# Extender_FPGA.net
KiCad netlist of a schematic drawn in Altium Designer
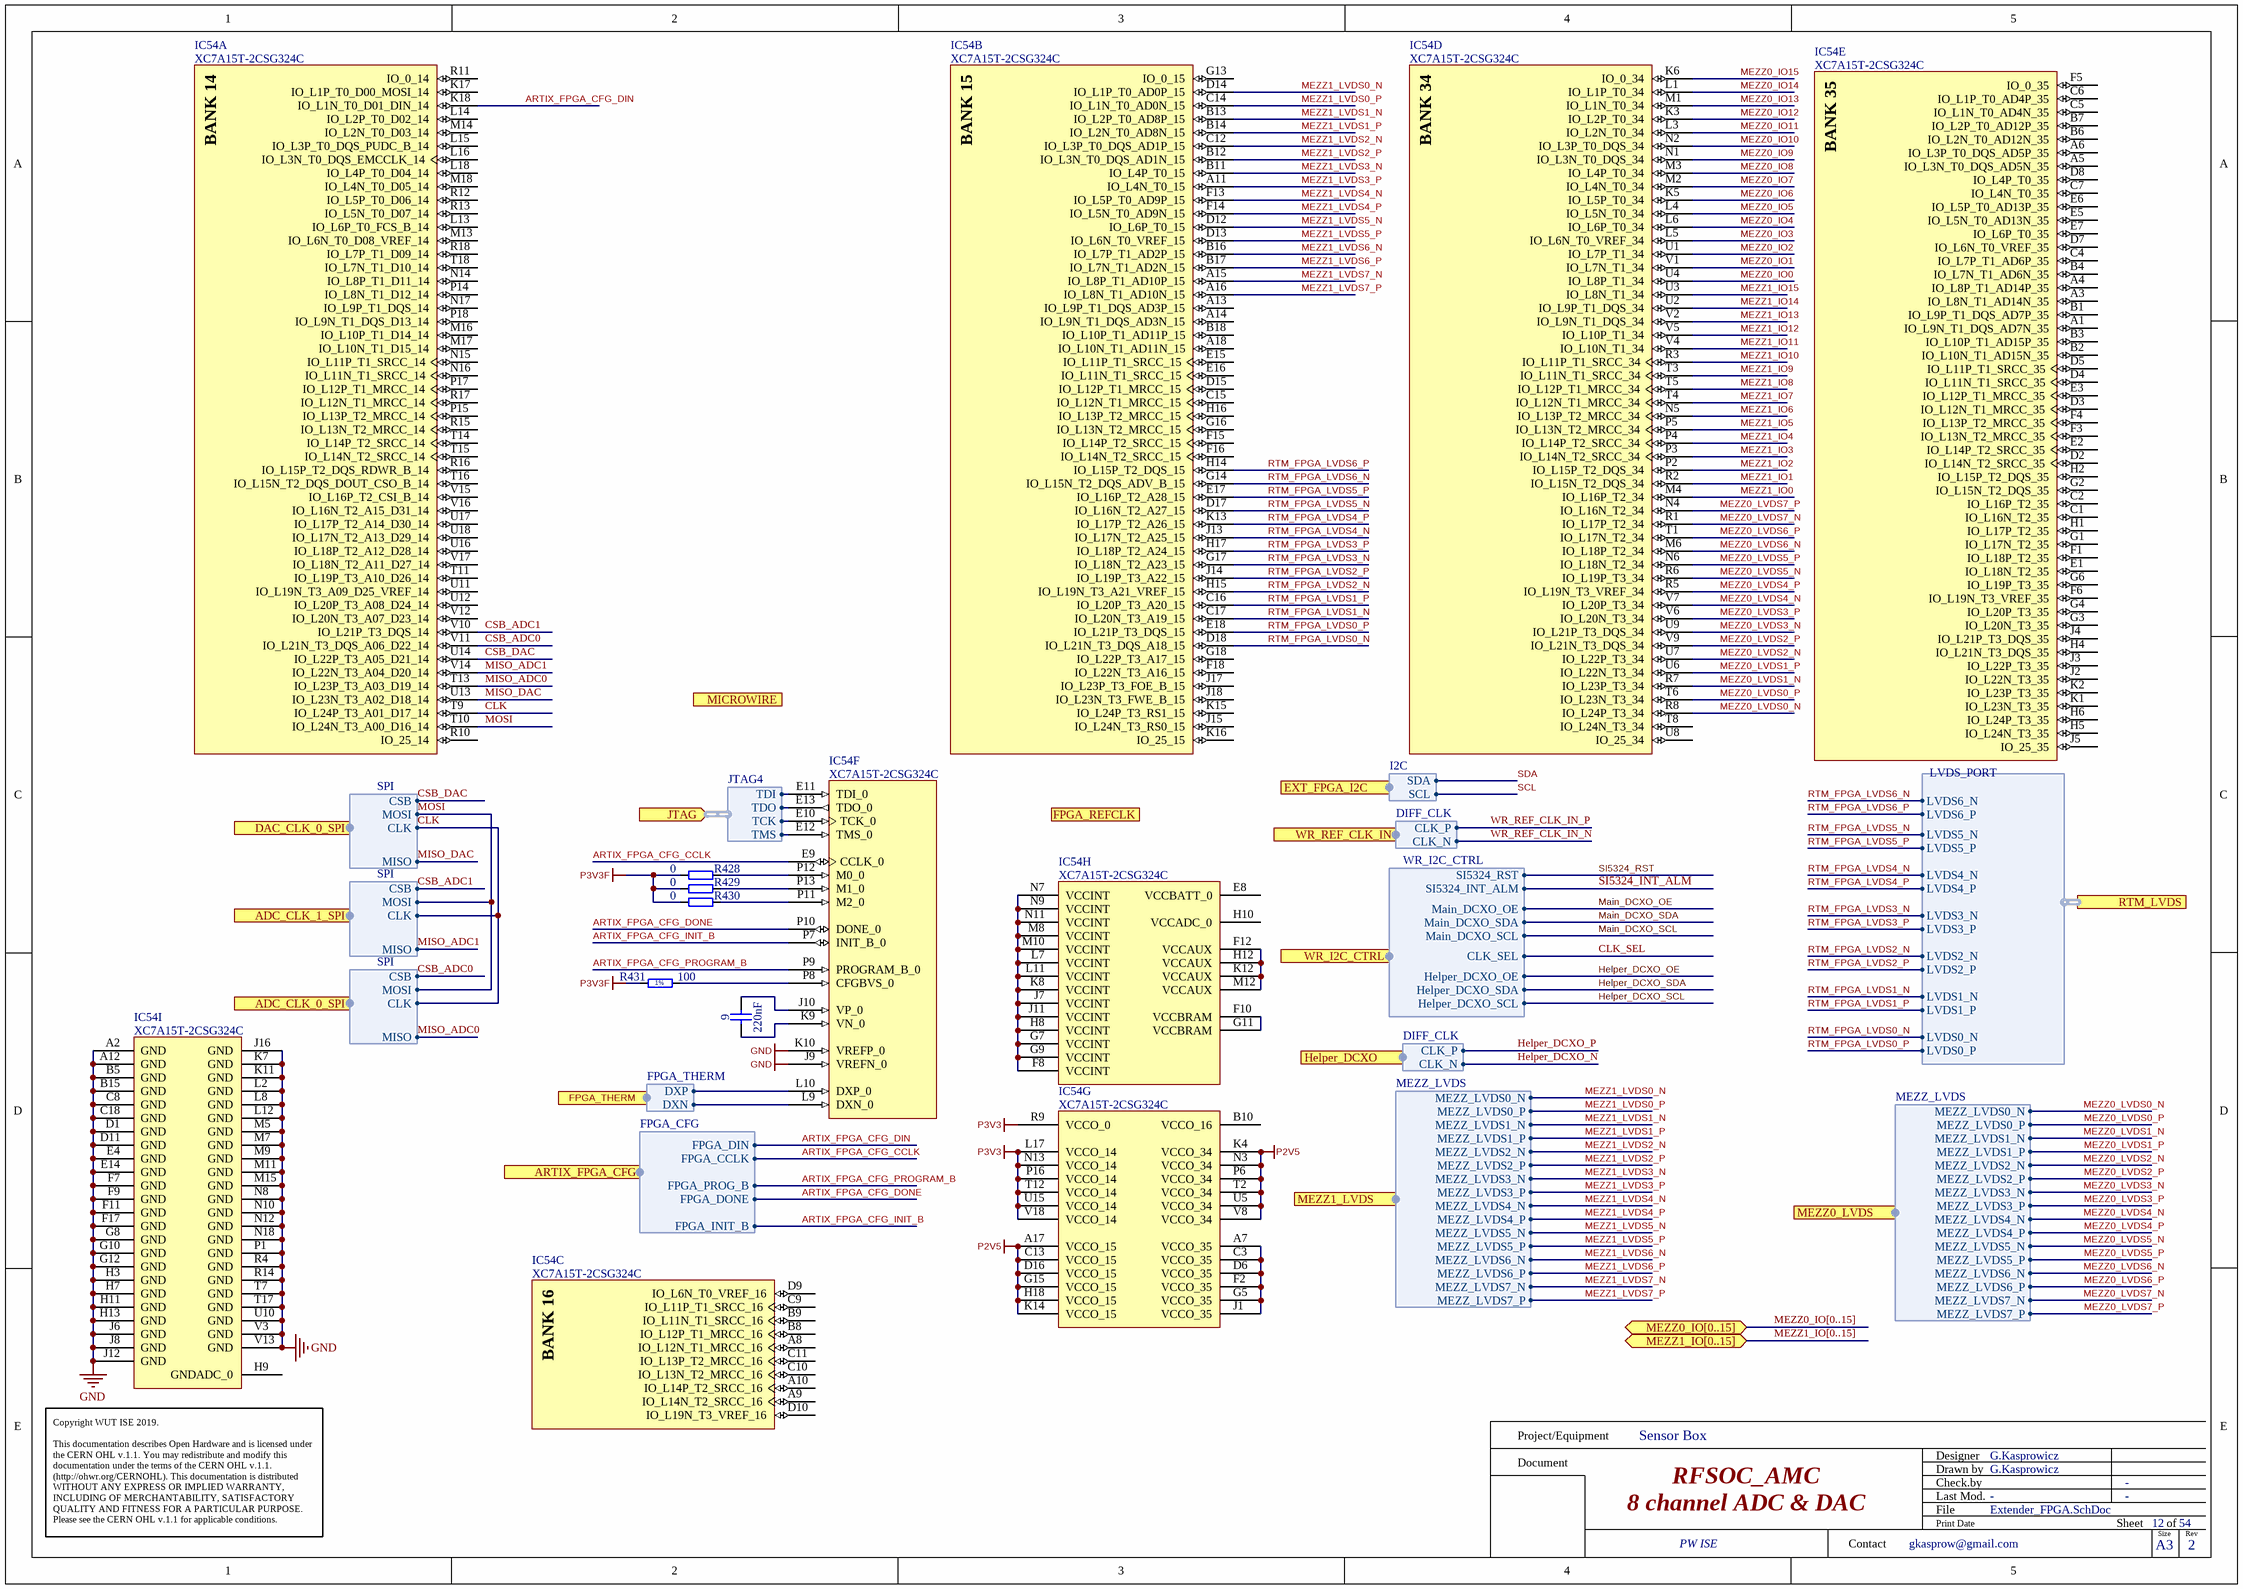
[diagram p0: Extender_FPGA.SchDoc]

(export (version "E")
  (design (tool "Eeschema 10.0.6"))
  (components
    (comp (ref "9")
      (value "220nF")
      (footprint "CAPC0603X33N")
      (description "Non-polarised capacitor")
      (fields
        (field (name "MANUFACTURER PART NUMBER") "CC0201_220NF_6.3V_20%_X5R")
        (field (name "MANUFACTURER") "GENERIC")
        (field (name "AUTHOR") "CERN DEM JLC")
      )
      (libsource (lib "Capacitors") (part "Capacitor - non polarized"))
    )
    (comp (ref "IC54")
      (value "XC7A15T-2CSG324C")
      (footprint "BGA324C80P18X18_1500X1500X150")
      (description "Artix-7 FPGA, 210 User I/Os, 0 GTP, 324-Ball BGA, Speed Grade 2, Commercial Grade, Pb-Free")
      (fields (field (name "MANUFACTURER") "XILINX") (field (name "AUTHOR") "CERN DEM MR"))
      (libsource (lib "ICs And Semiconductors") (part "XC7A15T-2CSG324C"))
    )
    (comp (ref "R428")
      (value "0")
      (footprint "RESC1005X40N")
      (description "Resistor")
      (fields
        (field (name "MANUFACTURER PART NUMBER") "R0402_0R_JUMPER")
        (field (name "MANUFACTURER") "GENERIC")
        (field (name "AUTHOR") "CERN DEM JLC")
      )
      (libsource (lib "Resistors") (part "Resistor"))
    )
    (comp (ref "R429")
      (value "0")
      (footprint "RESC1005X40N")
      (description "Resistor")
      (fields
        (field (name "MANUFACTURER PART NUMBER") "R0402_0R_JUMPER")
        (field (name "MANUFACTURER") "GENERIC")
        (field (name "AUTHOR") "CERN DEM JLC")
      )
      (libsource (lib "Resistors") (part "Resistor"))
    )
    (comp (ref "R430")
      (value "0")
      (footprint "RESC1005X40N")
      (description "Resistor")
      (fields
        (field (name "MANUFACTURER PART NUMBER") "R0402_0R_JUMPER")
        (field (name "MANUFACTURER") "GENERIC")
        (field (name "AUTHOR") "CERN DEM JLC")
      )
      (libsource (lib "Resistors") (part "Resistor"))
    )
    (comp (ref "R431")
      (value "100")
      (footprint "RESC1005X40N")
      (description "Resistor - 1%")
      (fields
        (field (name "MANUFACTURER PART NUMBER") "R0402_100R_1%_0.1W_100PPM_50V")
        (field (name "MANUFACTURER") "GENERIC")
        (field (name "AUTHOR") "CERN DEM JLC")
      )
      (libsource (lib "Resistors") (part "Resistor - 1%"))
    )
  )
  (nets
    (net (code "11") (name "/ARTIX_FPGA_CFG_CCLK") (class "Default")
      (node (ref "IC54") (pin "E9") (pinfunction "CCLK_0_E9") (pintype "bidirectional"))
    )
    (net (code "12") (name "/ARTIX_FPGA_CFG_DIN") (class "Default")
      (node (ref "IC54") (pin "K18") (pinfunction "IO_L1N_T0_D01_DIN_14_K18") (pintype "bidirectional"))
    )
    (net (code "13") (name "/ARTIX_FPGA_CFG_DONE") (class "Default")
      (node (ref "IC54") (pin "P10") (pinfunction "DONE_0_P10") (pintype "bidirectional"))
    )
    (net (code "14") (name "/ARTIX_FPGA_CFG_INIT_B") (class "Default")
      (node (ref "IC54") (pin "P7") (pinfunction "INIT_B_0_P7") (pintype "bidirectional"))
    )
    (net (code "15") (name "/ARTIX_FPGA_CFG_PROGRAM_B") (class "Default")
      (node (ref "IC54") (pin "P9") (pinfunction "PROGRAM_B_0_P9") (pintype "input"))
    )
    (net (code "16") (name "/CLK") (class "Default")
      (node (ref "IC54") (pin "T9") (pinfunction "IO_L24P_T3_A01_D17_14_T9") (pintype "bidirectional"))
    )
    (net (code "18") (name "/CSB_ADC0") (class "Default")
      (node (ref "IC54") (pin "V11") (pinfunction "IO_L21N_T3_DQS_A06_D22_14_V11") (pintype "bidirectional"))
    )
    (net (code "19") (name "/CSB_ADC1") (class "Default")
      (node (ref "IC54") (pin "V10") (pinfunction "IO_L21P_T3_DQS_14_V10") (pintype "bidirectional"))
    )
    (net (code "20") (name "/CSB_DAC") (class "Default")
      (node (ref "IC54") (pin "U14") (pinfunction "IO_L22P_T3_A05_D21_14_U14") (pintype "bidirectional"))
    )
    (net (code "21") (name "/DXN") (class "Default")
      (node (ref "IC54") (pin "L9") (pinfunction "DXN_0_L9") (pintype "input"))
    )
    (net (code "22") (name "/DXP") (class "Default")
      (node (ref "IC54") (pin "L10") (pinfunction "DXP_0_L10") (pintype "input"))
    )
    (net (code "29") (name "/MEZZ0_IO0") (class "Default")
      (node (ref "IC54") (pin "U4") (pinfunction "IO_L8P_T1_34_U4") (pintype "bidirectional"))
    )
    (net (code "30") (name "/MEZZ0_IO1") (class "Default")
      (node (ref "IC54") (pin "V1") (pinfunction "IO_L7N_T1_34_V1") (pintype "bidirectional"))
    )
    (net (code "31") (name "/MEZZ0_IO2") (class "Default")
      (node (ref "IC54") (pin "U1") (pinfunction "IO_L7P_T1_34_U1") (pintype "bidirectional"))
    )
    (net (code "32") (name "/MEZZ0_IO3") (class "Default")
      (node (ref "IC54") (pin "L5") (pinfunction "IO_L6N_T0_VREF_34_L5") (pintype "bidirectional"))
    )
    (net (code "33") (name "/MEZZ0_IO4") (class "Default")
      (node (ref "IC54") (pin "L6") (pinfunction "IO_L6P_T0_34_L6") (pintype "bidirectional"))
    )
    (net (code "34") (name "/MEZZ0_IO5") (class "Default")
      (node (ref "IC54") (pin "L4") (pinfunction "IO_L5N_T0_34_L4") (pintype "bidirectional"))
    )
    (net (code "35") (name "/MEZZ0_IO6") (class "Default")
      (node (ref "IC54") (pin "K5") (pinfunction "IO_L5P_T0_34_K5") (pintype "bidirectional"))
    )
    (net (code "36") (name "/MEZZ0_IO7") (class "Default")
      (node (ref "IC54") (pin "M2") (pinfunction "IO_L4N_T0_34_M2") (pintype "bidirectional"))
    )
    (net (code "37") (name "/MEZZ0_IO8") (class "Default")
      (node (ref "IC54") (pin "M3") (pinfunction "IO_L4P_T0_34_M3") (pintype "bidirectional"))
    )
    (net (code "38") (name "/MEZZ0_IO9") (class "Default")
      (node (ref "IC54") (pin "N1") (pinfunction "IO_L3N_T0_DQS_34_N1") (pintype "bidirectional"))
    )
    (net (code "39") (name "/MEZZ0_IO10") (class "Default")
      (node (ref "IC54") (pin "N2") (pinfunction "IO_L3P_T0_DQS_34_N2") (pintype "bidirectional"))
    )
    (net (code "40") (name "/MEZZ0_IO11") (class "Default")
      (node (ref "IC54") (pin "L3") (pinfunction "IO_L2N_T0_34_L3") (pintype "bidirectional"))
    )
    (net (code "41") (name "/MEZZ0_IO12") (class "Default")
      (node (ref "IC54") (pin "K3") (pinfunction "IO_L2P_T0_34_K3") (pintype "bidirectional"))
    )
    (net (code "42") (name "/MEZZ0_IO13") (class "Default")
      (node (ref "IC54") (pin "M1") (pinfunction "IO_L1N_T0_34_M1") (pintype "bidirectional"))
    )
    (net (code "43") (name "/MEZZ0_IO14") (class "Default")
      (node (ref "IC54") (pin "L1") (pinfunction "IO_L1P_T0_34_L1") (pintype "bidirectional"))
    )
    (net (code "44") (name "/MEZZ0_IO15") (class "Default")
      (node (ref "IC54") (pin "K6") (pinfunction "IO_0_34_K6") (pintype "bidirectional"))
    )
    (net (code "46") (name "/MEZZ0_LVDS0_N") (class "Default")
      (node (ref "IC54") (pin "R8") (pinfunction "IO_L24P_T3_34_R8") (pintype "bidirectional"))
    )
    (net (code "47") (name "/MEZZ0_LVDS0_P") (class "Default")
      (node (ref "IC54") (pin "T6") (pinfunction "IO_L23N_T3_34_T6") (pintype "bidirectional"))
    )
    (net (code "48") (name "/MEZZ0_LVDS1_N") (class "Default")
      (node (ref "IC54") (pin "R7") (pinfunction "IO_L23P_T3_34_R7") (pintype "bidirectional"))
    )
    (net (code "49") (name "/MEZZ0_LVDS1_P") (class "Default")
      (node (ref "IC54") (pin "U6") (pinfunction "IO_L22N_T3_34_U6") (pintype "bidirectional"))
    )
    (net (code "50") (name "/MEZZ0_LVDS2_N") (class "Default")
      (node (ref "IC54") (pin "U7") (pinfunction "IO_L22P_T3_34_U7") (pintype "bidirectional"))
    )
    (net (code "51") (name "/MEZZ0_LVDS2_P") (class "Default")
      (node (ref "IC54") (pin "V9") (pinfunction "IO_L21N_T3_DQS_34_V9") (pintype "bidirectional"))
    )
    (net (code "52") (name "/MEZZ0_LVDS3_N") (class "Default")
      (node (ref "IC54") (pin "U9") (pinfunction "IO_L21P_T3_DQS_34_U9") (pintype "bidirectional"))
    )
    (net (code "53") (name "/MEZZ0_LVDS3_P") (class "Default")
      (node (ref "IC54") (pin "V6") (pinfunction "IO_L20N_T3_34_V6") (pintype "bidirectional"))
    )
    (net (code "54") (name "/MEZZ0_LVDS4_N") (class "Default")
      (node (ref "IC54") (pin "V7") (pinfunction "IO_L20P_T3_34_V7") (pintype "bidirectional"))
    )
    (net (code "55") (name "/MEZZ0_LVDS4_P") (class "Default")
      (node (ref "IC54") (pin "R5") (pinfunction "IO_L19N_T3_VREF_34_R5") (pintype "bidirectional"))
    )
    (net (code "56") (name "/MEZZ0_LVDS5_N") (class "Default")
      (node (ref "IC54") (pin "R6") (pinfunction "IO_L19P_T3_34_R6") (pintype "bidirectional"))
    )
    (net (code "57") (name "/MEZZ0_LVDS5_P") (class "Default")
      (node (ref "IC54") (pin "N6") (pinfunction "IO_L18N_T2_34_N6") (pintype "bidirectional"))
    )
    (net (code "58") (name "/MEZZ0_LVDS6_N") (class "Default")
      (node (ref "IC54") (pin "M6") (pinfunction "IO_L18P_T2_34_M6") (pintype "bidirectional"))
    )
    (net (code "59") (name "/MEZZ0_LVDS6_P") (class "Default")
      (node (ref "IC54") (pin "T1") (pinfunction "IO_L17N_T2_34_T1") (pintype "bidirectional"))
    )
    (net (code "60") (name "/MEZZ0_LVDS7_N") (class "Default")
      (node (ref "IC54") (pin "R1") (pinfunction "IO_L17P_T2_34_R1") (pintype "bidirectional"))
    )
    (net (code "61") (name "/MEZZ0_LVDS7_P") (class "Default")
      (node (ref "IC54") (pin "N4") (pinfunction "IO_L16N_T2_34_N4") (pintype "bidirectional"))
    )
    (net (code "62") (name "/MEZZ1_IO0") (class "Default")
      (node (ref "IC54") (pin "M4") (pinfunction "IO_L16P_T2_34_M4") (pintype "bidirectional"))
    )
    (net (code "63") (name "/MEZZ1_IO1") (class "Default")
      (node (ref "IC54") (pin "R2") (pinfunction "IO_L15N_T2_DQS_34_R2") (pintype "bidirectional"))
    )
    (net (code "64") (name "/MEZZ1_IO2") (class "Default")
      (node (ref "IC54") (pin "P2") (pinfunction "IO_L15P_T2_DQS_34_P2") (pintype "bidirectional"))
    )
    (net (code "65") (name "/MEZZ1_IO3") (class "Default")
      (node (ref "IC54") (pin "P3") (pinfunction "IO_L14N_T2_SRCC_34_P3") (pintype "bidirectional"))
    )
    (net (code "66") (name "/MEZZ1_IO4") (class "Default")
      (node (ref "IC54") (pin "P4") (pinfunction "IO_L14P_T2_SRCC_34_P4") (pintype "bidirectional"))
    )
    (net (code "67") (name "/MEZZ1_IO5") (class "Default")
      (node (ref "IC54") (pin "P5") (pinfunction "IO_L13N_T2_MRCC_34_P5") (pintype "bidirectional"))
    )
    (net (code "68") (name "/MEZZ1_IO6") (class "Default")
      (node (ref "IC54") (pin "N5") (pinfunction "IO_L13P_T2_MRCC_34_N5") (pintype "bidirectional"))
    )
    (net (code "69") (name "/MEZZ1_IO7") (class "Default")
      (node (ref "IC54") (pin "T4") (pinfunction "IO_L12N_T1_MRCC_34_T4") (pintype "bidirectional"))
    )
    (net (code "70") (name "/MEZZ1_IO8") (class "Default")
      (node (ref "IC54") (pin "T5") (pinfunction "IO_L12P_T1_MRCC_34_T5") (pintype "bidirectional"))
    )
    (net (code "71") (name "/MEZZ1_IO9") (class "Default")
      (node (ref "IC54") (pin "T3") (pinfunction "IO_L11N_T1_SRCC_34_T3") (pintype "bidirectional"))
    )
    (net (code "72") (name "/MEZZ1_IO10") (class "Default")
      (node (ref "IC54") (pin "R3") (pinfunction "IO_L11P_T1_SRCC_34_R3") (pintype "bidirectional"))
    )
    (net (code "73") (name "/MEZZ1_IO11") (class "Default")
      (node (ref "IC54") (pin "V4") (pinfunction "IO_L10N_T1_34_V4") (pintype "bidirectional"))
    )
    (net (code "74") (name "/MEZZ1_IO12") (class "Default")
      (node (ref "IC54") (pin "V5") (pinfunction "IO_L10P_T1_34_V5") (pintype "bidirectional"))
    )
    (net (code "75") (name "/MEZZ1_IO13") (class "Default")
      (node (ref "IC54") (pin "V2") (pinfunction "IO_L9N_T1_DQS_34_V2") (pintype "bidirectional"))
    )
    (net (code "76") (name "/MEZZ1_IO14") (class "Default")
      (node (ref "IC54") (pin "U2") (pinfunction "IO_L9P_T1_DQS_34_U2") (pintype "bidirectional"))
    )
    (net (code "77") (name "/MEZZ1_IO15") (class "Default")
      (node (ref "IC54") (pin "U3") (pinfunction "IO_L8N_T1_34_U3") (pintype "bidirectional"))
    )
    (net (code "79") (name "/MEZZ1_LVDS0_N") (class "Default")
      (node (ref "IC54") (pin "D14") (pinfunction "IO_L1P_T0_AD0P_15_D14") (pintype "bidirectional"))
    )
    (net (code "80") (name "/MEZZ1_LVDS0_P") (class "Default")
      (node (ref "IC54") (pin "C14") (pinfunction "IO_L1N_T0_AD0N_15_C14") (pintype "bidirectional"))
    )
    (net (code "81") (name "/MEZZ1_LVDS1_N") (class "Default")
      (node (ref "IC54") (pin "B13") (pinfunction "IO_L2P_T0_AD8P_15_B13") (pintype "bidirectional"))
    )
    (net (code "82") (name "/MEZZ1_LVDS1_P") (class "Default")
      (node (ref "IC54") (pin "B14") (pinfunction "IO_L2N_T0_AD8N_15_B14") (pintype "bidirectional"))
    )
    (net (code "83") (name "/MEZZ1_LVDS2_N") (class "Default")
      (node (ref "IC54") (pin "C12") (pinfunction "IO_L3P_T0_DQS_AD1P_15_C12") (pintype "bidirectional"))
    )
    (net (code "84") (name "/MEZZ1_LVDS2_P") (class "Default")
      (node (ref "IC54") (pin "B12") (pinfunction "IO_L3N_T0_DQS_AD1N_15_B12") (pintype "bidirectional"))
    )
    (net (code "85") (name "/MEZZ1_LVDS3_N") (class "Default")
      (node (ref "IC54") (pin "B11") (pinfunction "IO_L4P_T0_15_B11") (pintype "bidirectional"))
    )
    (net (code "86") (name "/MEZZ1_LVDS3_P") (class "Default")
      (node (ref "IC54") (pin "A11") (pinfunction "IO_L4N_T0_15_A11") (pintype "bidirectional"))
    )
    (net (code "87") (name "/MEZZ1_LVDS4_N") (class "Default")
      (node (ref "IC54") (pin "F13") (pinfunction "IO_L5P_T0_AD9P_15_F13") (pintype "bidirectional"))
    )
    (net (code "88") (name "/MEZZ1_LVDS4_P") (class "Default")
      (node (ref "IC54") (pin "F14") (pinfunction "IO_L5N_T0_AD9N_15_F14") (pintype "bidirectional"))
    )
    (net (code "89") (name "/MEZZ1_LVDS5_N") (class "Default")
      (node (ref "IC54") (pin "D12") (pinfunction "IO_L6P_T0_15_D12") (pintype "bidirectional"))
    )
    (net (code "90") (name "/MEZZ1_LVDS5_P") (class "Default")
      (node (ref "IC54") (pin "D13") (pinfunction "IO_L6N_T0_VREF_15_D13") (pintype "bidirectional"))
    )
    (net (code "91") (name "/MEZZ1_LVDS6_N") (class "Default")
      (node (ref "IC54") (pin "B16") (pinfunction "IO_L7P_T1_AD2P_15_B16") (pintype "bidirectional"))
    )
    (net (code "92") (name "/MEZZ1_LVDS6_P") (class "Default")
      (node (ref "IC54") (pin "B17") (pinfunction "IO_L7N_T1_AD2N_15_B17") (pintype "bidirectional"))
    )
    (net (code "93") (name "/MEZZ1_LVDS7_N") (class "Default")
      (node (ref "IC54") (pin "A15") (pinfunction "IO_L8P_T1_AD10P_15_A15") (pintype "bidirectional"))
    )
    (net (code "94") (name "/MEZZ1_LVDS7_P") (class "Default")
      (node (ref "IC54") (pin "A16") (pinfunction "IO_L8N_T1_AD10N_15_A16") (pintype "bidirectional"))
    )
    (net (code "96") (name "/MISO_ADC0") (class "Default")
      (node (ref "IC54") (pin "T13") (pinfunction "IO_L23P_T3_A03_D19_14_T13") (pintype "bidirectional"))
    )
    (net (code "97") (name "/MISO_ADC1") (class "Default")
      (node (ref "IC54") (pin "V14") (pinfunction "IO_L22N_T3_A04_D20_14_V14") (pintype "bidirectional"))
    )
    (net (code "98") (name "/MISO_DAC") (class "Default")
      (node (ref "IC54") (pin "U13") (pinfunction "IO_L23N_T3_A02_D18_14_U13") (pintype "bidirectional"))
    )
    (net (code "99") (name "/MOSI") (class "Default")
      (node (ref "IC54") (pin "T10") (pinfunction "IO_L24N_T3_A00_D16_14_T10") (pintype "bidirectional"))
    )
    (net (code "103") (name "/RTM_FPGA_LVDS0_N") (class "Default")
      (node (ref "IC54") (pin "D18") (pinfunction "IO_L21N_T3_DQS_A18_15_D18") (pintype "bidirectional"))
    )
    (net (code "104") (name "/RTM_FPGA_LVDS0_P") (class "Default")
      (node (ref "IC54") (pin "E18") (pinfunction "IO_L21P_T3_DQS_15_E18") (pintype "bidirectional"))
    )
    (net (code "105") (name "/RTM_FPGA_LVDS1_N") (class "Default")
      (node (ref "IC54") (pin "C17") (pinfunction "IO_L20N_T3_A19_15_C17") (pintype "bidirectional"))
    )
    (net (code "106") (name "/RTM_FPGA_LVDS1_P") (class "Default")
      (node (ref "IC54") (pin "C16") (pinfunction "IO_L20P_T3_A20_15_C16") (pintype "bidirectional"))
    )
    (net (code "107") (name "/RTM_FPGA_LVDS2_N") (class "Default")
      (node (ref "IC54") (pin "H15") (pinfunction "IO_L19N_T3_A21_VREF_15_H15") (pintype "bidirectional"))
    )
    (net (code "108") (name "/RTM_FPGA_LVDS2_P") (class "Default")
      (node (ref "IC54") (pin "J14") (pinfunction "IO_L19P_T3_A22_15_J14") (pintype "bidirectional"))
    )
    (net (code "109") (name "/RTM_FPGA_LVDS3_N") (class "Default")
      (node (ref "IC54") (pin "G17") (pinfunction "IO_L18N_T2_A23_15_G17") (pintype "bidirectional"))
    )
    (net (code "110") (name "/RTM_FPGA_LVDS3_P") (class "Default")
      (node (ref "IC54") (pin "H17") (pinfunction "IO_L18P_T2_A24_15_H17") (pintype "bidirectional"))
    )
    (net (code "111") (name "/RTM_FPGA_LVDS4_N") (class "Default")
      (node (ref "IC54") (pin "J13") (pinfunction "IO_L17N_T2_A25_15_J13") (pintype "bidirectional"))
    )
    (net (code "112") (name "/RTM_FPGA_LVDS4_P") (class "Default")
      (node (ref "IC54") (pin "K13") (pinfunction "IO_L17P_T2_A26_15_K13") (pintype "bidirectional"))
    )
    (net (code "113") (name "/RTM_FPGA_LVDS5_N") (class "Default")
      (node (ref "IC54") (pin "D17") (pinfunction "IO_L16N_T2_A27_15_D17") (pintype "bidirectional"))
    )
    (net (code "114") (name "/RTM_FPGA_LVDS5_P") (class "Default")
      (node (ref "IC54") (pin "E17") (pinfunction "IO_L16P_T2_A28_15_E17") (pintype "bidirectional"))
    )
    (net (code "115") (name "/RTM_FPGA_LVDS6_N") (class "Default")
      (node (ref "IC54") (pin "G14") (pinfunction "IO_L15N_T2_DQS_ADV_B_15_G14") (pintype "bidirectional"))
    )
    (net (code "116") (name "/RTM_FPGA_LVDS6_P") (class "Default")
      (node (ref "IC54") (pin "H14") (pinfunction "IO_L15P_T2_DQS_15_H14") (pintype "bidirectional"))
    )
    (net (code "121") (name "/TCK") (class "Default")
      (node (ref "IC54") (pin "E10") (pinfunction "TCK_0_E10") (pintype "input"))
    )
    (net (code "122") (name "/TDI") (class "Default")
      (node (ref "IC54") (pin "E11") (pinfunction "TDI_0_E11") (pintype "input"))
    )
    (net (code "123") (name "/TDO") (class "Default")
      (node (ref "IC54") (pin "E13") (pinfunction "TDO_0_E13") (pintype "output"))
    )
    (net (code "124") (name "/TMS") (class "Default")
      (node (ref "IC54") (pin "E12") (pinfunction "TMS_0_E12") (pintype "input"))
    )
    (net (code "136") (name "GND") (class "Default")
      (node (ref "IC54") (pin "A12") (pinfunction "GND_A12") (pintype "power_in"))
      (node (ref "IC54") (pin "A2") (pinfunction "GND_A2") (pintype "power_in"))
      (node (ref "IC54") (pin "B15") (pinfunction "GND_B15") (pintype "power_in"))
      (node (ref "IC54") (pin "B5") (pinfunction "GND_B5") (pintype "power_in"))
      (node (ref "IC54") (pin "C18") (pinfunction "GND_C18") (pintype "power_in"))
      (node (ref "IC54") (pin "C8") (pinfunction "GND_C8") (pintype "power_in"))
      (node (ref "IC54") (pin "D1") (pinfunction "GND_D1") (pintype "power_in"))
      (node (ref "IC54") (pin "D11") (pinfunction "GND_D11") (pintype "power_in"))
      (node (ref "IC54") (pin "E14") (pinfunction "GND_E14") (pintype "power_in"))
      (node (ref "IC54") (pin "E4") (pinfunction "GND_E4") (pintype "power_in"))
      (node (ref "IC54") (pin "F11") (pinfunction "GND_F11") (pintype "power_in"))
      (node (ref "IC54") (pin "F17") (pinfunction "GND_F17") (pintype "power_in"))
      (node (ref "IC54") (pin "F7") (pinfunction "GND_F7") (pintype "power_in"))
      (node (ref "IC54") (pin "F9") (pinfunction "GND_F9") (pintype "power_in"))
      (node (ref "IC54") (pin "G10") (pinfunction "GND_G10") (pintype "power_in"))
      (node (ref "IC54") (pin "G12") (pinfunction "GND_G12") (pintype "power_in"))
      (node (ref "IC54") (pin "G8") (pinfunction "GND_G8") (pintype "power_in"))
      (node (ref "IC54") (pin "H11") (pinfunction "GND_H11") (pintype "power_in"))
      (node (ref "IC54") (pin "H13") (pinfunction "GND_H13") (pintype "power_in"))
      (node (ref "IC54") (pin "H3") (pinfunction "GND_H3") (pintype "power_in"))
      (node (ref "IC54") (pin "H7") (pinfunction "GND_H7") (pintype "power_in"))
      (node (ref "IC54") (pin "J12") (pinfunction "GND_J12") (pintype "power_in"))
      (node (ref "IC54") (pin "J16") (pinfunction "GND_J16") (pintype "power_in"))
      (node (ref "IC54") (pin "J6") (pinfunction "GND_J6") (pintype "power_in"))
      (node (ref "IC54") (pin "J8") (pinfunction "GND_J8") (pintype "power_in"))
      (node (ref "IC54") (pin "J9") (pinfunction "VREFN_0_J9") (pintype "input"))
      (node (ref "IC54") (pin "K10") (pinfunction "VREFP_0_K10") (pintype "input"))
      (node (ref "IC54") (pin "K11") (pinfunction "GND_K11") (pintype "power_in"))
      (node (ref "IC54") (pin "K7") (pinfunction "GND_K7") (pintype "power_in"))
      (node (ref "IC54") (pin "L12") (pinfunction "GND_L12") (pintype "power_in"))
      (node (ref "IC54") (pin "L2") (pinfunction "GND_L2") (pintype "power_in"))
      (node (ref "IC54") (pin "L8") (pinfunction "GND_L8") (pintype "power_in"))
      (node (ref "IC54") (pin "M11") (pinfunction "GND_M11") (pintype "power_in"))
      (node (ref "IC54") (pin "M15") (pinfunction "GND_M15") (pintype "power_in"))
      (node (ref "IC54") (pin "M5") (pinfunction "GND_M5") (pintype "power_in"))
      (node (ref "IC54") (pin "M7") (pinfunction "GND_M7") (pintype "power_in"))
      (node (ref "IC54") (pin "M9") (pinfunction "GND_M9") (pintype "power_in"))
      (node (ref "IC54") (pin "N10") (pinfunction "GND_N10") (pintype "power_in"))
      (node (ref "IC54") (pin "N12") (pinfunction "GND_N12") (pintype "power_in"))
      (node (ref "IC54") (pin "N18") (pinfunction "GND_N18") (pintype "power_in"))
      (node (ref "IC54") (pin "N8") (pinfunction "GND_N8") (pintype "power_in"))
      (node (ref "IC54") (pin "P1") (pinfunction "GND_P1") (pintype "power_in"))
      (node (ref "IC54") (pin "R14") (pinfunction "GND_R14") (pintype "power_in"))
      (node (ref "IC54") (pin "R4") (pinfunction "GND_R4") (pintype "power_in"))
      (node (ref "IC54") (pin "T17") (pinfunction "GND_T17") (pintype "power_in"))
      (node (ref "IC54") (pin "T7") (pinfunction "GND_T7") (pintype "power_in"))
      (node (ref "IC54") (pin "U10") (pinfunction "GND_U10") (pintype "power_in"))
      (node (ref "IC54") (pin "V13") (pinfunction "GND_V13") (pintype "power_in"))
      (node (ref "IC54") (pin "V3") (pinfunction "GND_V3") (pintype "power_in"))
    )
    (net (code "137") (name "Net-(IC54F-CFGBVS_0)") (class "Default")
      (node (ref "IC54") (pin "P8") (pinfunction "CFGBVS_0_P8") (pintype "input"))
      (node (ref "R431") (pin "2") (pinfunction "2_2") (pintype "passive"))
    )
    (net (code "138") (name "Net-(IC54F-M0_0)") (class "Default")
      (node (ref "IC54") (pin "P12") (pinfunction "M0_0_P12") (pintype "input"))
      (node (ref "R428") (pin "2") (pinfunction "2_2") (pintype "passive"))
    )
    (net (code "139") (name "Net-(IC54F-M1_0)") (class "Default")
      (node (ref "IC54") (pin "P13") (pinfunction "M1_0_P13") (pintype "input"))
      (node (ref "R429") (pin "2") (pinfunction "2_2") (pintype "passive"))
    )
    (net (code "140") (name "Net-(IC54F-M2_0)") (class "Default")
      (node (ref "IC54") (pin "P11") (pinfunction "M2_0_P11") (pintype "input"))
      (node (ref "R430") (pin "2") (pinfunction "2_2") (pintype "passive"))
    )
    (net (code "141") (name "Net-(IC54F-VN_0)") (class "Default")
      (node (ref "9") (pin "1") (pinfunction "1_1") (pintype "passive"))
      (node (ref "IC54") (pin "K9") (pinfunction "VN_0_K9") (pintype "input"))
    )
    (net (code "142") (name "Net-(IC54F-VP_0)") (class "Default")
      (node (ref "9") (pin "2") (pinfunction "2_2") (pintype "passive"))
      (node (ref "IC54") (pin "J10") (pinfunction "VP_0_J10") (pintype "input"))
    )
    (net (code "143") (name "Net-(IC54G-VCCO_35-PadA7)") (class "Default")
      (node (ref "IC54") (pin "A7") (pinfunction "VCCO_35_A7") (pintype "power_in"))
      (node (ref "IC54") (pin "C3") (pinfunction "VCCO_35_C3") (pintype "power_in"))
      (node (ref "IC54") (pin "D6") (pinfunction "VCCO_35_D6") (pintype "power_in"))
      (node (ref "IC54") (pin "F2") (pinfunction "VCCO_35_F2") (pintype "power_in"))
      (node (ref "IC54") (pin "G5") (pinfunction "VCCO_35_G5") (pintype "power_in"))
      (node (ref "IC54") (pin "J1") (pinfunction "VCCO_35_J1") (pintype "power_in"))
    )
    (net (code "144") (name "Net-(IC54H-VCCAUX-PadF12)") (class "Default")
      (node (ref "IC54") (pin "F12") (pinfunction "VCCAUX_F12") (pintype "power_in"))
      (node (ref "IC54") (pin "H12") (pinfunction "VCCAUX_H12") (pintype "power_in"))
      (node (ref "IC54") (pin "K12") (pinfunction "VCCAUX_K12") (pintype "power_in"))
      (node (ref "IC54") (pin "M12") (pinfunction "VCCAUX_M12") (pintype "power_in"))
    )
    (net (code "145") (name "Net-(IC54H-VCCBRAM-PadF10)") (class "Default")
      (node (ref "IC54") (pin "F10") (pinfunction "VCCBRAM_F10") (pintype "power_in"))
      (node (ref "IC54") (pin "G11") (pinfunction "VCCBRAM_G11") (pintype "power_in"))
    )
    (net (code "146") (name "Net-(IC54H-VCCINT-PadF8)") (class "Default")
      (node (ref "IC54") (pin "F8") (pinfunction "VCCINT_F8") (pintype "power_in"))
      (node (ref "IC54") (pin "G7") (pinfunction "VCCINT_G7") (pintype "power_in"))
      (node (ref "IC54") (pin "G9") (pinfunction "VCCINT_G9") (pintype "power_in"))
      (node (ref "IC54") (pin "H8") (pinfunction "VCCINT_H8") (pintype "power_in"))
      (node (ref "IC54") (pin "J11") (pinfunction "VCCINT_J11") (pintype "power_in"))
      (node (ref "IC54") (pin "J7") (pinfunction "VCCINT_J7") (pintype "power_in"))
      (node (ref "IC54") (pin "K8") (pinfunction "VCCINT_K8") (pintype "power_in"))
      (node (ref "IC54") (pin "L11") (pinfunction "VCCINT_L11") (pintype "power_in"))
      (node (ref "IC54") (pin "L7") (pinfunction "VCCINT_L7") (pintype "power_in"))
      (node (ref "IC54") (pin "M10") (pinfunction "VCCINT_M10") (pintype "power_in"))
      (node (ref "IC54") (pin "M8") (pinfunction "VCCINT_M8") (pintype "power_in"))
      (node (ref "IC54") (pin "N11") (pinfunction "VCCINT_N11") (pintype "power_in"))
      (node (ref "IC54") (pin "N7") (pinfunction "VCCINT_N7") (pintype "power_in"))
      (node (ref "IC54") (pin "N9") (pinfunction "VCCINT_N9") (pintype "power_in"))
    )
    (net (code "147") (name "P2V5") (class "Default")
      (node (ref "IC54") (pin "A17") (pinfunction "VCCO_15_A17") (pintype "power_in"))
      (node (ref "IC54") (pin "C13") (pinfunction "VCCO_15_C13") (pintype "power_in"))
      (node (ref "IC54") (pin "D16") (pinfunction "VCCO_15_D16") (pintype "power_in"))
      (node (ref "IC54") (pin "G15") (pinfunction "VCCO_15_G15") (pintype "power_in"))
      (node (ref "IC54") (pin "H18") (pinfunction "VCCO_15_H18") (pintype "power_in"))
      (node (ref "IC54") (pin "K14") (pinfunction "VCCO_15_K14") (pintype "power_in"))
      (node (ref "IC54") (pin "K4") (pinfunction "VCCO_34_K4") (pintype "power_in"))
      (node (ref "IC54") (pin "N3") (pinfunction "VCCO_34_N3") (pintype "power_in"))
      (node (ref "IC54") (pin "P6") (pinfunction "VCCO_34_P6") (pintype "power_in"))
      (node (ref "IC54") (pin "T2") (pinfunction "VCCO_34_T2") (pintype "power_in"))
      (node (ref "IC54") (pin "U5") (pinfunction "VCCO_34_U5") (pintype "power_in"))
      (node (ref "IC54") (pin "V8") (pinfunction "VCCO_34_V8") (pintype "power_in"))
    )
    (net (code "148") (name "P3V3") (class "Default")
      (node (ref "IC54") (pin "L17") (pinfunction "VCCO_14_L17") (pintype "power_in"))
      (node (ref "IC54") (pin "N13") (pinfunction "VCCO_14_N13") (pintype "power_in"))
      (node (ref "IC54") (pin "P16") (pinfunction "VCCO_14_P16") (pintype "power_in"))
      (node (ref "IC54") (pin "R9") (pinfunction "VCCO_0_R9") (pintype "power_in"))
      (node (ref "IC54") (pin "T12") (pinfunction "VCCO_14_T12") (pintype "power_in"))
      (node (ref "IC54") (pin "U15") (pinfunction "VCCO_14_U15") (pintype "power_in"))
      (node (ref "IC54") (pin "V18") (pinfunction "VCCO_14_V18") (pintype "power_in"))
    )
    (net (code "149") (name "P3V3F") (class "Default")
      (node (ref "R428") (pin "1") (pinfunction "1_1") (pintype "passive"))
      (node (ref "R429") (pin "1") (pinfunction "1_1") (pintype "passive"))
      (node (ref "R430") (pin "1") (pinfunction "1_1") (pintype "passive"))
      (node (ref "R431") (pin "1") (pinfunction "1_1") (pintype "passive"))
    )
    (net (code "150") (name "unconnected-(IC54A-IO_0_14-PadR11)") (class "Default")
      (node (ref "IC54") (pin "R11") (pinfunction "IO_0_14_R11") (pintype "bidirectional"))
    )
    (net (code "151") (name "unconnected-(IC54A-IO_25_14-PadR10)") (class "Default")
      (node (ref "IC54") (pin "R10") (pinfunction "IO_25_14_R10") (pintype "bidirectional"))
    )
    (net (code "152") (name "unconnected-(IC54A-IO_L1P_T0_D00_MOSI_14-PadK17)") (class "Default")
      (node (ref "IC54") (pin "K17") (pinfunction "IO_L1P_T0_D00_MOSI_14_K17") (pintype "bidirectional"))
    )
    (net (code "153") (name "unconnected-(IC54A-IO_L2N_T0_D03_14-PadM14)") (class "Default")
      (node (ref "IC54") (pin "M14") (pinfunction "IO_L2N_T0_D03_14_M14") (pintype "bidirectional"))
    )
    (net (code "154") (name "unconnected-(IC54A-IO_L2P_T0_D02_14-PadL14)") (class "Default")
      (node (ref "IC54") (pin "L14") (pinfunction "IO_L2P_T0_D02_14_L14") (pintype "bidirectional"))
    )
    (net (code "155") (name "unconnected-(IC54A-IO_L3N_T0_DQS_EMCCLK_14-PadL16)") (class "Default")
      (node (ref "IC54") (pin "L16") (pinfunction "IO_L3N_T0_DQS_EMCCLK_14_L16") (pintype "bidirectional"))
    )
    (net (code "156") (name "unconnected-(IC54A-IO_L3P_T0_DQS_PUDC_B_14-PadL15)") (class "Default")
      (node (ref "IC54") (pin "L15") (pinfunction "IO_L3P_T0_DQS_PUDC_B_14_L15") (pintype "bidirectional"))
    )
    (net (code "157") (name "unconnected-(IC54A-IO_L4N_T0_D05_14-PadM18)") (class "Default")
      (node (ref "IC54") (pin "M18") (pinfunction "IO_L4N_T0_D05_14_M18") (pintype "bidirectional"))
    )
    (net (code "158") (name "unconnected-(IC54A-IO_L4P_T0_D04_14-PadL18)") (class "Default")
      (node (ref "IC54") (pin "L18") (pinfunction "IO_L4P_T0_D04_14_L18") (pintype "bidirectional"))
    )
    (net (code "159") (name "unconnected-(IC54A-IO_L5N_T0_D07_14-PadR13)") (class "Default")
      (node (ref "IC54") (pin "R13") (pinfunction "IO_L5N_T0_D07_14_R13") (pintype "bidirectional"))
    )
    (net (code "160") (name "unconnected-(IC54A-IO_L5P_T0_D06_14-PadR12)") (class "Default")
      (node (ref "IC54") (pin "R12") (pinfunction "IO_L5P_T0_D06_14_R12") (pintype "bidirectional"))
    )
    (net (code "161") (name "unconnected-(IC54A-IO_L6N_T0_D08_VREF_14-PadM13)") (class "Default")
      (node (ref "IC54") (pin "M13") (pinfunction "IO_L6N_T0_D08_VREF_14_M13") (pintype "bidirectional"))
    )
    (net (code "162") (name "unconnected-(IC54A-IO_L6P_T0_FCS_B_14-PadL13)") (class "Default")
      (node (ref "IC54") (pin "L13") (pinfunction "IO_L6P_T0_FCS_B_14_L13") (pintype "bidirectional"))
    )
    (net (code "163") (name "unconnected-(IC54A-IO_L7N_T1_D10_14-PadT18)") (class "Default")
      (node (ref "IC54") (pin "T18") (pinfunction "IO_L7N_T1_D10_14_T18") (pintype "bidirectional"))
    )
    (net (code "164") (name "unconnected-(IC54A-IO_L7P_T1_D09_14-PadR18)") (class "Default")
      (node (ref "IC54") (pin "R18") (pinfunction "IO_L7P_T1_D09_14_R18") (pintype "bidirectional"))
    )
    (net (code "165") (name "unconnected-(IC54A-IO_L8N_T1_D12_14-PadP14)") (class "Default")
      (node (ref "IC54") (pin "P14") (pinfunction "IO_L8N_T1_D12_14_P14") (pintype "bidirectional"))
    )
    (net (code "166") (name "unconnected-(IC54A-IO_L8P_T1_D11_14-PadN14)") (class "Default")
      (node (ref "IC54") (pin "N14") (pinfunction "IO_L8P_T1_D11_14_N14") (pintype "bidirectional"))
    )
    (net (code "167") (name "unconnected-(IC54A-IO_L9N_T1_DQS_D13_14-PadP18)") (class "Default")
      (node (ref "IC54") (pin "P18") (pinfunction "IO_L9N_T1_DQS_D13_14_P18") (pintype "bidirectional"))
    )
    (net (code "168") (name "unconnected-(IC54A-IO_L9P_T1_DQS_14-PadN17)") (class "Default")
      (node (ref "IC54") (pin "N17") (pinfunction "IO_L9P_T1_DQS_14_N17") (pintype "bidirectional"))
    )
    (net (code "169") (name "unconnected-(IC54A-IO_L10N_T1_D15_14-PadM17)") (class "Default")
      (node (ref "IC54") (pin "M17") (pinfunction "IO_L10N_T1_D15_14_M17") (pintype "bidirectional"))
    )
    (net (code "170") (name "unconnected-(IC54A-IO_L10P_T1_D14_14-PadM16)") (class "Default")
      (node (ref "IC54") (pin "M16") (pinfunction "IO_L10P_T1_D14_14_M16") (pintype "bidirectional"))
    )
    (net (code "171") (name "unconnected-(IC54A-IO_L11N_T1_SRCC_14-PadN16)") (class "Default")
      (node (ref "IC54") (pin "N16") (pinfunction "IO_L11N_T1_SRCC_14_N16") (pintype "bidirectional"))
    )
    (net (code "172") (name "unconnected-(IC54A-IO_L11P_T1_SRCC_14-PadN15)") (class "Default")
      (node (ref "IC54") (pin "N15") (pinfunction "IO_L11P_T1_SRCC_14_N15") (pintype "bidirectional"))
    )
    (net (code "173") (name "unconnected-(IC54A-IO_L12N_T1_MRCC_14-PadR17)") (class "Default")
      (node (ref "IC54") (pin "R17") (pinfunction "IO_L12N_T1_MRCC_14_R17") (pintype "bidirectional"))
    )
    (net (code "174") (name "unconnected-(IC54A-IO_L12P_T1_MRCC_14-PadP17)") (class "Default")
      (node (ref "IC54") (pin "P17") (pinfunction "IO_L12P_T1_MRCC_14_P17") (pintype "bidirectional"))
    )
    (net (code "175") (name "unconnected-(IC54A-IO_L13N_T2_MRCC_14-PadR15)") (class "Default")
      (node (ref "IC54") (pin "R15") (pinfunction "IO_L13N_T2_MRCC_14_R15") (pintype "bidirectional"))
    )
    (net (code "176") (name "unconnected-(IC54A-IO_L13P_T2_MRCC_14-PadP15)") (class "Default")
      (node (ref "IC54") (pin "P15") (pinfunction "IO_L13P_T2_MRCC_14_P15") (pintype "bidirectional"))
    )
    (net (code "177") (name "unconnected-(IC54A-IO_L14N_T2_SRCC_14-PadT15)") (class "Default")
      (node (ref "IC54") (pin "T15") (pinfunction "IO_L14N_T2_SRCC_14_T15") (pintype "bidirectional"))
    )
    (net (code "178") (name "unconnected-(IC54A-IO_L14P_T2_SRCC_14-PadT14)") (class "Default")
      (node (ref "IC54") (pin "T14") (pinfunction "IO_L14P_T2_SRCC_14_T14") (pintype "bidirectional"))
    )
    (net (code "179") (name "unconnected-(IC54A-IO_L15N_T2_DQS_DOUT_CSO_B_14-PadT16)") (class "Default")
      (node (ref "IC54") (pin "T16") (pinfunction "IO_L15N_T2_DQS_DOUT_CSO_B_14_T16") (pintype "bidirectional"))
    )
    (net (code "180") (name "unconnected-(IC54A-IO_L15P_T2_DQS_RDWR_B_14-PadR16)") (class "Default")
      (node (ref "IC54") (pin "R16") (pinfunction "IO_L15P_T2_DQS_RDWR_B_14_R16") (pintype "bidirectional"))
    )
    (net (code "181") (name "unconnected-(IC54A-IO_L16N_T2_A15_D31_14-PadV16)") (class "Default")
      (node (ref "IC54") (pin "V16") (pinfunction "IO_L16N_T2_A15_D31_14_V16") (pintype "bidirectional"))
    )
    (net (code "182") (name "unconnected-(IC54A-IO_L16P_T2_CSI_B_14-PadV15)") (class "Default")
      (node (ref "IC54") (pin "V15") (pinfunction "IO_L16P_T2_CSI_B_14_V15") (pintype "bidirectional"))
    )
    (net (code "183") (name "unconnected-(IC54A-IO_L17N_T2_A13_D29_14-PadU18)") (class "Default")
      (node (ref "IC54") (pin "U18") (pinfunction "IO_L17N_T2_A13_D29_14_U18") (pintype "bidirectional"))
    )
    (net (code "184") (name "unconnected-(IC54A-IO_L17P_T2_A14_D30_14-PadU17)") (class "Default")
      (node (ref "IC54") (pin "U17") (pinfunction "IO_L17P_T2_A14_D30_14_U17") (pintype "bidirectional"))
    )
    (net (code "185") (name "unconnected-(IC54A-IO_L18N_T2_A11_D27_14-PadV17)") (class "Default")
      (node (ref "IC54") (pin "V17") (pinfunction "IO_L18N_T2_A11_D27_14_V17") (pintype "bidirectional"))
    )
    (net (code "186") (name "unconnected-(IC54A-IO_L18P_T2_A12_D28_14-PadU16)") (class "Default")
      (node (ref "IC54") (pin "U16") (pinfunction "IO_L18P_T2_A12_D28_14_U16") (pintype "bidirectional"))
    )
    (net (code "187") (name "unconnected-(IC54A-IO_L19N_T3_A09_D25_VREF_14-PadU11)") (class "Default")
      (node (ref "IC54") (pin "U11") (pinfunction "IO_L19N_T3_A09_D25_VREF_14_U11") (pintype "bidirectional"))
    )
    (net (code "188") (name "unconnected-(IC54A-IO_L19P_T3_A10_D26_14-PadT11)") (class "Default")
      (node (ref "IC54") (pin "T11") (pinfunction "IO_L19P_T3_A10_D26_14_T11") (pintype "bidirectional"))
    )
    (net (code "189") (name "unconnected-(IC54A-IO_L20N_T3_A07_D23_14-PadV12)") (class "Default")
      (node (ref "IC54") (pin "V12") (pinfunction "IO_L20N_T3_A07_D23_14_V12") (pintype "bidirectional"))
    )
    (net (code "190") (name "unconnected-(IC54A-IO_L20P_T3_A08_D24_14-PadU12)") (class "Default")
      (node (ref "IC54") (pin "U12") (pinfunction "IO_L20P_T3_A08_D24_14_U12") (pintype "bidirectional"))
    )
    (net (code "191") (name "unconnected-(IC54B-IO_0_15-PadG13)") (class "Default")
      (node (ref "IC54") (pin "G13") (pinfunction "IO_0_15_G13") (pintype "bidirectional"))
    )
    (net (code "192") (name "unconnected-(IC54B-IO_25_15-PadK16)") (class "Default")
      (node (ref "IC54") (pin "K16") (pinfunction "IO_25_15_K16") (pintype "bidirectional"))
    )
    (net (code "193") (name "unconnected-(IC54B-IO_L9N_T1_DQS_AD3N_15-PadA14)") (class "Default")
      (node (ref "IC54") (pin "A14") (pinfunction "IO_L9N_T1_DQS_AD3N_15_A14") (pintype "bidirectional"))
    )
    (net (code "194") (name "unconnected-(IC54B-IO_L9P_T1_DQS_AD3P_15-PadA13)") (class "Default")
      (node (ref "IC54") (pin "A13") (pinfunction "IO_L9P_T1_DQS_AD3P_15_A13") (pintype "bidirectional"))
    )
    (net (code "195") (name "unconnected-(IC54B-IO_L10N_T1_AD11N_15-PadA18)") (class "Default")
      (node (ref "IC54") (pin "A18") (pinfunction "IO_L10N_T1_AD11N_15_A18") (pintype "bidirectional"))
    )
    (net (code "196") (name "unconnected-(IC54B-IO_L10P_T1_AD11P_15-PadB18)") (class "Default")
      (node (ref "IC54") (pin "B18") (pinfunction "IO_L10P_T1_AD11P_15_B18") (pintype "bidirectional"))
    )
    (net (code "197") (name "unconnected-(IC54B-IO_L11N_T1_SRCC_15-PadE16)") (class "Default")
      (node (ref "IC54") (pin "E16") (pinfunction "IO_L11N_T1_SRCC_15_E16") (pintype "bidirectional"))
    )
    (net (code "198") (name "unconnected-(IC54B-IO_L11P_T1_SRCC_15-PadE15)") (class "Default")
      (node (ref "IC54") (pin "E15") (pinfunction "IO_L11P_T1_SRCC_15_E15") (pintype "bidirectional"))
    )
    (net (code "199") (name "unconnected-(IC54B-IO_L12N_T1_MRCC_15-PadC15)") (class "Default")
      (node (ref "IC54") (pin "C15") (pinfunction "IO_L12N_T1_MRCC_15_C15") (pintype "bidirectional"))
    )
    (net (code "200") (name "unconnected-(IC54B-IO_L12P_T1_MRCC_15-PadD15)") (class "Default")
      (node (ref "IC54") (pin "D15") (pinfunction "IO_L12P_T1_MRCC_15_D15") (pintype "bidirectional"))
    )
    (net (code "201") (name "unconnected-(IC54B-IO_L13N_T2_MRCC_15-PadG16)") (class "Default")
      (node (ref "IC54") (pin "G16") (pinfunction "IO_L13N_T2_MRCC_15_G16") (pintype "bidirectional"))
    )
    (net (code "202") (name "unconnected-(IC54B-IO_L13P_T2_MRCC_15-PadH16)") (class "Default")
      (node (ref "IC54") (pin "H16") (pinfunction "IO_L13P_T2_MRCC_15_H16") (pintype "bidirectional"))
    )
    (net (code "203") (name "unconnected-(IC54B-IO_L14N_T2_SRCC_15-PadF16)") (class "Default")
      (node (ref "IC54") (pin "F16") (pinfunction "IO_L14N_T2_SRCC_15_F16") (pintype "bidirectional"))
    )
    (net (code "204") (name "unconnected-(IC54B-IO_L14P_T2_SRCC_15-PadF15)") (class "Default")
      (node (ref "IC54") (pin "F15") (pinfunction "IO_L14P_T2_SRCC_15_F15") (pintype "bidirectional"))
    )
    (net (code "205") (name "unconnected-(IC54B-IO_L22N_T3_A16_15-PadF18)") (class "Default")
      (node (ref "IC54") (pin "F18") (pinfunction "IO_L22N_T3_A16_15_F18") (pintype "bidirectional"))
    )
    (net (code "206") (name "unconnected-(IC54B-IO_L22P_T3_A17_15-PadG18)") (class "Default")
      (node (ref "IC54") (pin "G18") (pinfunction "IO_L22P_T3_A17_15_G18") (pintype "bidirectional"))
    )
    (net (code "207") (name "unconnected-(IC54B-IO_L23N_T3_FWE_B_15-PadJ18)") (class "Default")
      (node (ref "IC54") (pin "J18") (pinfunction "IO_L23N_T3_FWE_B_15_J18") (pintype "bidirectional"))
    )
    (net (code "208") (name "unconnected-(IC54B-IO_L23P_T3_FOE_B_15-PadJ17)") (class "Default")
      (node (ref "IC54") (pin "J17") (pinfunction "IO_L23P_T3_FOE_B_15_J17") (pintype "bidirectional"))
    )
    (net (code "209") (name "unconnected-(IC54B-IO_L24N_T3_RS0_15-PadJ15)") (class "Default")
      (node (ref "IC54") (pin "J15") (pinfunction "IO_L24N_T3_RS0_15_J15") (pintype "bidirectional"))
    )
    (net (code "210") (name "unconnected-(IC54B-IO_L24P_T3_RS1_15-PadK15)") (class "Default")
      (node (ref "IC54") (pin "K15") (pinfunction "IO_L24P_T3_RS1_15_K15") (pintype "bidirectional"))
    )
    (net (code "211") (name "unconnected-(IC54C-IO_L6N_T0_VREF_16-PadD9)") (class "Default")
      (node (ref "IC54") (pin "D9") (pinfunction "IO_L6N_T0_VREF_16_D9") (pintype "bidirectional"))
    )
    (net (code "212") (name "unconnected-(IC54C-IO_L11N_T1_SRCC_16-PadB9)") (class "Default")
      (node (ref "IC54") (pin "B9") (pinfunction "IO_L11N_T1_SRCC_16_B9") (pintype "bidirectional"))
    )
    (net (code "213") (name "unconnected-(IC54C-IO_L11P_T1_SRCC_16-PadC9)") (class "Default")
      (node (ref "IC54") (pin "C9") (pinfunction "IO_L11P_T1_SRCC_16_C9") (pintype "bidirectional"))
    )
    (net (code "214") (name "unconnected-(IC54C-IO_L12N_T1_MRCC_16-PadA8)") (class "Default")
      (node (ref "IC54") (pin "A8") (pinfunction "IO_L12N_T1_MRCC_16_A8") (pintype "bidirectional"))
    )
    (net (code "215") (name "unconnected-(IC54C-IO_L12P_T1_MRCC_16-PadB8)") (class "Default")
      (node (ref "IC54") (pin "B8") (pinfunction "IO_L12P_T1_MRCC_16_B8") (pintype "bidirectional"))
    )
    (net (code "216") (name "unconnected-(IC54C-IO_L13N_T2_MRCC_16-PadC10)") (class "Default")
      (node (ref "IC54") (pin "C10") (pinfunction "IO_L13N_T2_MRCC_16_C10") (pintype "bidirectional"))
    )
    (net (code "217") (name "unconnected-(IC54C-IO_L13P_T2_MRCC_16-PadC11)") (class "Default")
      (node (ref "IC54") (pin "C11") (pinfunction "IO_L13P_T2_MRCC_16_C11") (pintype "bidirectional"))
    )
    (net (code "218") (name "unconnected-(IC54C-IO_L14N_T2_SRCC_16-PadA9)") (class "Default")
      (node (ref "IC54") (pin "A9") (pinfunction "IO_L14N_T2_SRCC_16_A9") (pintype "bidirectional"))
    )
    (net (code "219") (name "unconnected-(IC54C-IO_L14P_T2_SRCC_16-PadA10)") (class "Default")
      (node (ref "IC54") (pin "A10") (pinfunction "IO_L14P_T2_SRCC_16_A10") (pintype "bidirectional"))
    )
    (net (code "220") (name "unconnected-(IC54C-IO_L19N_T3_VREF_16-PadD10)") (class "Default")
      (node (ref "IC54") (pin "D10") (pinfunction "IO_L19N_T3_VREF_16_D10") (pintype "bidirectional"))
    )
    (net (code "221") (name "unconnected-(IC54D-IO_25_34-PadU8)") (class "Default")
      (node (ref "IC54") (pin "U8") (pinfunction "IO_25_34_U8") (pintype "bidirectional"))
    )
    (net (code "222") (name "unconnected-(IC54D-IO_L24N_T3_34-PadT8)") (class "Default")
      (node (ref "IC54") (pin "T8") (pinfunction "IO_L24N_T3_34_T8") (pintype "bidirectional"))
    )
    (net (code "223") (name "unconnected-(IC54E-IO_0_35-PadF5)") (class "Default")
      (node (ref "IC54") (pin "F5") (pinfunction "IO_0_35_F5") (pintype "bidirectional"))
    )
    (net (code "224") (name "unconnected-(IC54E-IO_25_35-PadJ5)") (class "Default")
      (node (ref "IC54") (pin "J5") (pinfunction "IO_25_35_J5") (pintype "bidirectional"))
    )
    (net (code "225") (name "unconnected-(IC54E-IO_L1N_T0_AD4N_35-PadC5)") (class "Default")
      (node (ref "IC54") (pin "C5") (pinfunction "IO_L1N_T0_AD4N_35_C5") (pintype "bidirectional"))
    )
    (net (code "226") (name "unconnected-(IC54E-IO_L1P_T0_AD4P_35-PadC6)") (class "Default")
      (node (ref "IC54") (pin "C6") (pinfunction "IO_L1P_T0_AD4P_35_C6") (pintype "bidirectional"))
    )
    (net (code "227") (name "unconnected-(IC54E-IO_L2N_T0_AD12N_35-PadB6)") (class "Default")
      (node (ref "IC54") (pin "B6") (pinfunction "IO_L2N_T0_AD12N_35_B6") (pintype "bidirectional"))
    )
    (net (code "228") (name "unconnected-(IC54E-IO_L2P_T0_AD12P_35-PadB7)") (class "Default")
      (node (ref "IC54") (pin "B7") (pinfunction "IO_L2P_T0_AD12P_35_B7") (pintype "bidirectional"))
    )
    (net (code "229") (name "unconnected-(IC54E-IO_L3N_T0_DQS_AD5N_35-PadA5)") (class "Default")
      (node (ref "IC54") (pin "A5") (pinfunction "IO_L3N_T0_DQS_AD5N_35_A5") (pintype "bidirectional"))
    )
    (net (code "230") (name "unconnected-(IC54E-IO_L3P_T0_DQS_AD5P_35-PadA6)") (class "Default")
      (node (ref "IC54") (pin "A6") (pinfunction "IO_L3P_T0_DQS_AD5P_35_A6") (pintype "bidirectional"))
    )
    (net (code "231") (name "unconnected-(IC54E-IO_L4N_T0_35-PadC7)") (class "Default")
      (node (ref "IC54") (pin "C7") (pinfunction "IO_L4N_T0_35_C7") (pintype "bidirectional"))
    )
    (net (code "232") (name "unconnected-(IC54E-IO_L4P_T0_35-PadD8)") (class "Default")
      (node (ref "IC54") (pin "D8") (pinfunction "IO_L4P_T0_35_D8") (pintype "bidirectional"))
    )
    (net (code "233") (name "unconnected-(IC54E-IO_L5N_T0_AD13N_35-PadE5)") (class "Default")
      (node (ref "IC54") (pin "E5") (pinfunction "IO_L5N_T0_AD13N_35_E5") (pintype "bidirectional"))
    )
    (net (code "234") (name "unconnected-(IC54E-IO_L5P_T0_AD13P_35-PadE6)") (class "Default")
      (node (ref "IC54") (pin "E6") (pinfunction "IO_L5P_T0_AD13P_35_E6") (pintype "bidirectional"))
    )
    (net (code "235") (name "unconnected-(IC54E-IO_L6N_T0_VREF_35-PadD7)") (class "Default")
      (node (ref "IC54") (pin "D7") (pinfunction "IO_L6N_T0_VREF_35_D7") (pintype "bidirectional"))
    )
    (net (code "236") (name "unconnected-(IC54E-IO_L6P_T0_35-PadE7)") (class "Default")
      (node (ref "IC54") (pin "E7") (pinfunction "IO_L6P_T0_35_E7") (pintype "bidirectional"))
    )
    (net (code "237") (name "unconnected-(IC54E-IO_L7N_T1_AD6N_35-PadB4)") (class "Default")
      (node (ref "IC54") (pin "B4") (pinfunction "IO_L7N_T1_AD6N_35_B4") (pintype "bidirectional"))
    )
    (net (code "238") (name "unconnected-(IC54E-IO_L7P_T1_AD6P_35-PadC4)") (class "Default")
      (node (ref "IC54") (pin "C4") (pinfunction "IO_L7P_T1_AD6P_35_C4") (pintype "bidirectional"))
    )
    (net (code "239") (name "unconnected-(IC54E-IO_L8N_T1_AD14N_35-PadA3)") (class "Default")
      (node (ref "IC54") (pin "A3") (pinfunction "IO_L8N_T1_AD14N_35_A3") (pintype "bidirectional"))
    )
    (net (code "240") (name "unconnected-(IC54E-IO_L8P_T1_AD14P_35-PadA4)") (class "Default")
      (node (ref "IC54") (pin "A4") (pinfunction "IO_L8P_T1_AD14P_35_A4") (pintype "bidirectional"))
    )
    (net (code "241") (name "unconnected-(IC54E-IO_L9N_T1_DQS_AD7N_35-PadA1)") (class "Default")
      (node (ref "IC54") (pin "A1") (pinfunction "IO_L9N_T1_DQS_AD7N_35_A1") (pintype "bidirectional"))
    )
    (net (code "242") (name "unconnected-(IC54E-IO_L9P_T1_DQS_AD7P_35-PadB1)") (class "Default")
      (node (ref "IC54") (pin "B1") (pinfunction "IO_L9P_T1_DQS_AD7P_35_B1") (pintype "bidirectional"))
    )
    (net (code "243") (name "unconnected-(IC54E-IO_L10N_T1_AD15N_35-PadB2)") (class "Default")
      (node (ref "IC54") (pin "B2") (pinfunction "IO_L10N_T1_AD15N_35_B2") (pintype "bidirectional"))
    )
    (net (code "244") (name "unconnected-(IC54E-IO_L10P_T1_AD15P_35-PadB3)") (class "Default")
      (node (ref "IC54") (pin "B3") (pinfunction "IO_L10P_T1_AD15P_35_B3") (pintype "bidirectional"))
    )
    (net (code "245") (name "unconnected-(IC54E-IO_L11N_T1_SRCC_35-PadD4)") (class "Default")
      (node (ref "IC54") (pin "D4") (pinfunction "IO_L11N_T1_SRCC_35_D4") (pintype "bidirectional"))
    )
    (net (code "246") (name "unconnected-(IC54E-IO_L11P_T1_SRCC_35-PadD5)") (class "Default")
      (node (ref "IC54") (pin "D5") (pinfunction "IO_L11P_T1_SRCC_35_D5") (pintype "bidirectional"))
    )
    (net (code "247") (name "unconnected-(IC54E-IO_L12N_T1_MRCC_35-PadD3)") (class "Default")
      (node (ref "IC54") (pin "D3") (pinfunction "IO_L12N_T1_MRCC_35_D3") (pintype "bidirectional"))
    )
    (net (code "248") (name "unconnected-(IC54E-IO_L12P_T1_MRCC_35-PadE3)") (class "Default")
      (node (ref "IC54") (pin "E3") (pinfunction "IO_L12P_T1_MRCC_35_E3") (pintype "bidirectional"))
    )
    (net (code "249") (name "unconnected-(IC54E-IO_L13N_T2_MRCC_35-PadF3)") (class "Default")
      (node (ref "IC54") (pin "F3") (pinfunction "IO_L13N_T2_MRCC_35_F3") (pintype "bidirectional"))
    )
    (net (code "250") (name "unconnected-(IC54E-IO_L13P_T2_MRCC_35-PadF4)") (class "Default")
      (node (ref "IC54") (pin "F4") (pinfunction "IO_L13P_T2_MRCC_35_F4") (pintype "bidirectional"))
    )
    (net (code "251") (name "unconnected-(IC54E-IO_L14N_T2_SRCC_35-PadD2)") (class "Default")
      (node (ref "IC54") (pin "D2") (pinfunction "IO_L14N_T2_SRCC_35_D2") (pintype "bidirectional"))
    )
    (net (code "252") (name "unconnected-(IC54E-IO_L14P_T2_SRCC_35-PadE2)") (class "Default")
      (node (ref "IC54") (pin "E2") (pinfunction "IO_L14P_T2_SRCC_35_E2") (pintype "bidirectional"))
    )
    (net (code "253") (name "unconnected-(IC54E-IO_L15N_T2_DQS_35-PadG2)") (class "Default")
      (node (ref "IC54") (pin "G2") (pinfunction "IO_L15N_T2_DQS_35_G2") (pintype "bidirectional"))
    )
    (net (code "254") (name "unconnected-(IC54E-IO_L15P_T2_DQS_35-PadH2)") (class "Default")
      (node (ref "IC54") (pin "H2") (pinfunction "IO_L15P_T2_DQS_35_H2") (pintype "bidirectional"))
    )
    (net (code "255") (name "unconnected-(IC54E-IO_L16N_T2_35-PadC1)") (class "Default")
      (node (ref "IC54") (pin "C1") (pinfunction "IO_L16N_T2_35_C1") (pintype "bidirectional"))
    )
    (net (code "256") (name "unconnected-(IC54E-IO_L16P_T2_35-PadC2)") (class "Default")
      (node (ref "IC54") (pin "C2") (pinfunction "IO_L16P_T2_35_C2") (pintype "bidirectional"))
    )
    (net (code "257") (name "unconnected-(IC54E-IO_L17N_T2_35-PadG1)") (class "Default")
      (node (ref "IC54") (pin "G1") (pinfunction "IO_L17N_T2_35_G1") (pintype "bidirectional"))
    )
    (net (code "258") (name "unconnected-(IC54E-IO_L17P_T2_35-PadH1)") (class "Default")
      (node (ref "IC54") (pin "H1") (pinfunction "IO_L17P_T2_35_H1") (pintype "bidirectional"))
    )
    (net (code "259") (name "unconnected-(IC54E-IO_L18N_T2_35-PadE1)") (class "Default")
      (node (ref "IC54") (pin "E1") (pinfunction "IO_L18N_T2_35_E1") (pintype "bidirectional"))
    )
    (net (code "260") (name "unconnected-(IC54E-IO_L18P_T2_35-PadF1)") (class "Default")
      (node (ref "IC54") (pin "F1") (pinfunction "IO_L18P_T2_35_F1") (pintype "bidirectional"))
    )
    (net (code "261") (name "unconnected-(IC54E-IO_L19N_T3_VREF_35-PadF6)") (class "Default")
      (node (ref "IC54") (pin "F6") (pinfunction "IO_L19N_T3_VREF_35_F6") (pintype "bidirectional"))
    )
    (net (code "262") (name "unconnected-(IC54E-IO_L19P_T3_35-PadG6)") (class "Default")
      (node (ref "IC54") (pin "G6") (pinfunction "IO_L19P_T3_35_G6") (pintype "bidirectional"))
    )
    (net (code "263") (name "unconnected-(IC54E-IO_L20N_T3_35-PadG3)") (class "Default")
      (node (ref "IC54") (pin "G3") (pinfunction "IO_L20N_T3_35_G3") (pintype "bidirectional"))
    )
    (net (code "264") (name "unconnected-(IC54E-IO_L20P_T3_35-PadG4)") (class "Default")
      (node (ref "IC54") (pin "G4") (pinfunction "IO_L20P_T3_35_G4") (pintype "bidirectional"))
    )
    (net (code "265") (name "unconnected-(IC54E-IO_L21N_T3_DQS_35-PadH4)") (class "Default")
      (node (ref "IC54") (pin "H4") (pinfunction "IO_L21N_T3_DQS_35_H4") (pintype "bidirectional"))
    )
    (net (code "266") (name "unconnected-(IC54E-IO_L21P_T3_DQS_35-PadJ4)") (class "Default")
      (node (ref "IC54") (pin "J4") (pinfunction "IO_L21P_T3_DQS_35_J4") (pintype "bidirectional"))
    )
    (net (code "267") (name "unconnected-(IC54E-IO_L22N_T3_35-PadJ2)") (class "Default")
      (node (ref "IC54") (pin "J2") (pinfunction "IO_L22N_T3_35_J2") (pintype "bidirectional"))
    )
    (net (code "268") (name "unconnected-(IC54E-IO_L22P_T3_35-PadJ3)") (class "Default")
      (node (ref "IC54") (pin "J3") (pinfunction "IO_L22P_T3_35_J3") (pintype "bidirectional"))
    )
    (net (code "269") (name "unconnected-(IC54E-IO_L23N_T3_35-PadK1)") (class "Default")
      (node (ref "IC54") (pin "K1") (pinfunction "IO_L23N_T3_35_K1") (pintype "bidirectional"))
    )
    (net (code "270") (name "unconnected-(IC54E-IO_L23P_T3_35-PadK2)") (class "Default")
      (node (ref "IC54") (pin "K2") (pinfunction "IO_L23P_T3_35_K2") (pintype "bidirectional"))
    )
    (net (code "271") (name "unconnected-(IC54E-IO_L24N_T3_35-PadH5)") (class "Default")
      (node (ref "IC54") (pin "H5") (pinfunction "IO_L24N_T3_35_H5") (pintype "bidirectional"))
    )
    (net (code "272") (name "unconnected-(IC54E-IO_L24P_T3_35-PadH6)") (class "Default")
      (node (ref "IC54") (pin "H6") (pinfunction "IO_L24P_T3_35_H6") (pintype "bidirectional"))
    )
    (net (code "273") (name "unconnected-(IC54G-VCCO_16-PadB10)") (class "Default")
      (node (ref "IC54") (pin "B10") (pinfunction "VCCO_16_B10") (pintype "power_in"))
    )
    (net (code "274") (name "unconnected-(IC54H-VCCADC_0-PadH10)") (class "Default")
      (node (ref "IC54") (pin "H10") (pinfunction "VCCADC_0_H10") (pintype "power_in"))
    )
    (net (code "275") (name "unconnected-(IC54H-VCCBATT_0-PadE8)") (class "Default")
      (node (ref "IC54") (pin "E8") (pinfunction "VCCBATT_0_E8") (pintype "power_in"))
    )
    (net (code "276") (name "unconnected-(IC54I-GNDADC_0-PadH9)") (class "Default")
      (node (ref "IC54") (pin "H9") (pinfunction "GNDADC_0_H9") (pintype "power_in"))
    )
  )
)
